# car_onboard.net
KiCad netlist of a schematic drawn in EAGLE
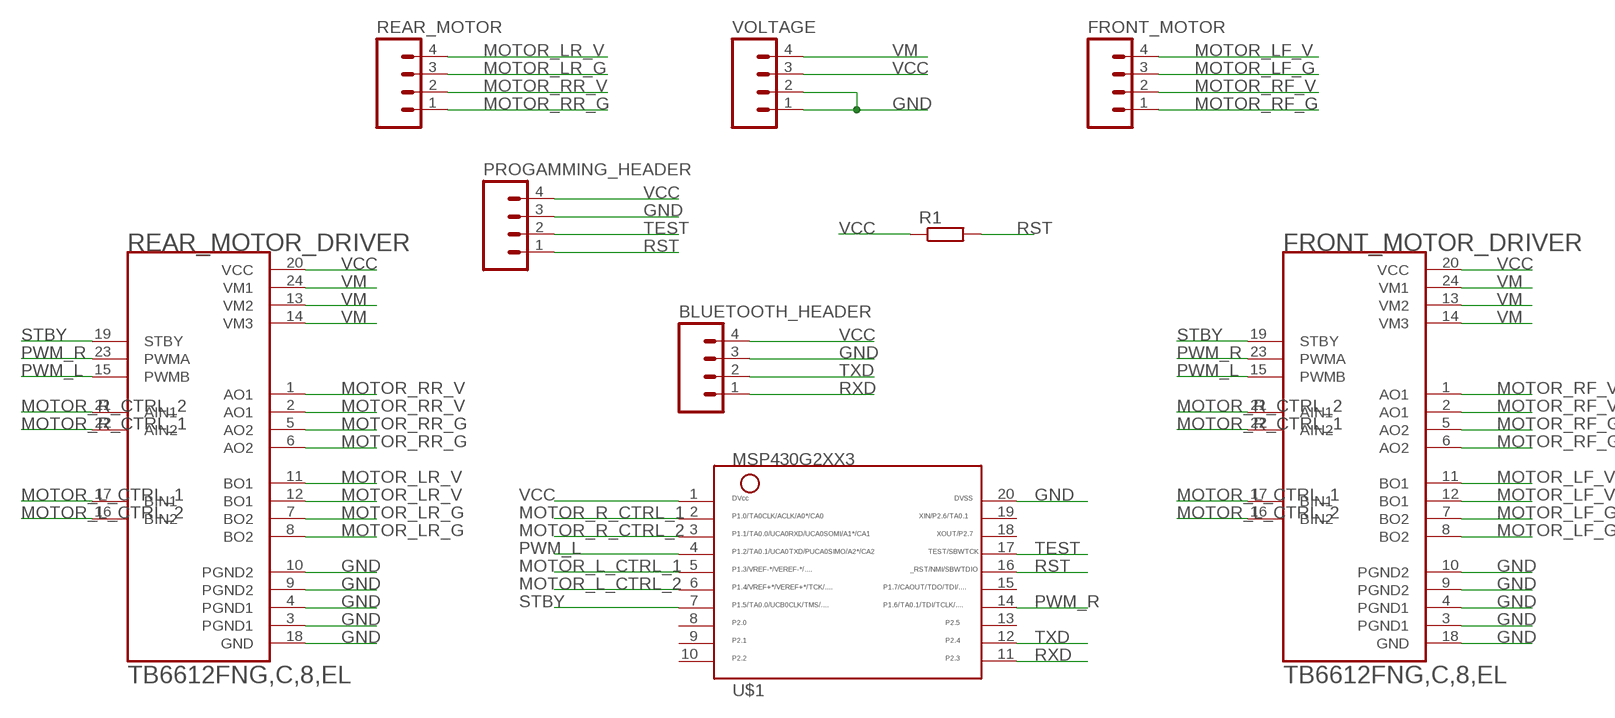
[diagram p0: schematic, sheet 1]

(export (version "E")
  (design (tool "Eeschema 10.0.6"))
  (components
    (comp (ref "BLUETOOTH_HEADER")
      (value "HEADER_1X04LOCK")
      (footprint "eagle-import:1X04_LOCK")
      (libsource (lib "eagle-import") (part "HEADER_1X04LOCK"))
    )
    (comp (ref "FRONT_MOTOR")
      (value "HEADER_1X04LOCK")
      (footprint "eagle-import:1X04_LOCK")
      (libsource (lib "eagle-import") (part "HEADER_1X04LOCK"))
    )
    (comp (ref "FRONT_MOTOR_DRIVER")
      (value "TB6612FNG,C,8,EL")
      (footprint "eagle-import:SOP65P760X160-24N")
      (fields (field (name "MF") "Toshiba"))
      (libsource (lib "eagle-import") (part "TB6612FNG,C,8,EL"))
    )
    (comp (ref "PROGAMMING_HEADER")
      (value "HEADER_1X04LOCK")
      (footprint "eagle-import:1X04_LOCK")
      (libsource (lib "eagle-import") (part "HEADER_1X04LOCK"))
    )
    (comp (ref "R1")
      (value "R-EU_R1206")
      (footprint "eagle-import:R1206")
      (libsource (lib "eagle-import") (part "R-EU_R1206"))
    )
    (comp (ref "REAR_MOTOR")
      (value "HEADER_1X04LOCK")
      (footprint "eagle-import:1X04_LOCK")
      (libsource (lib "eagle-import") (part "HEADER_1X04LOCK"))
    )
    (comp (ref "REAR_MOTOR_DRIVER")
      (value "TB6612FNG,C,8,EL")
      (footprint "eagle-import:SOP65P760X160-24N")
      (fields (field (name "MF") "Toshiba"))
      (libsource (lib "eagle-import") (part "TB6612FNG,C,8,EL"))
    )
    (comp (ref "U$1")
      (value "MSP430G2XX3TSSOP")
      (footprint "eagle-import:PW20")
      (libsource (lib "eagle-import") (part "MSP430G2XX3TSSOP"))
    )
    (comp (ref "VOLTAGE")
      (value "HEADER_1X04LOCK")
      (footprint "eagle-import:1X04_LOCK")
      (libsource (lib "eagle-import") (part "HEADER_1X04LOCK"))
    )
  )
  (nets
    (net (code "1") (name "/GND") (class "Default")
      (node (ref "BLUETOOTH_HEADER") (pin "3") (pinfunction "3_3") (pintype "passive"))
      (node (ref "FRONT_MOTOR_DRIVER") (pin "10") (pinfunction "PGND2_10") (pintype "passive"))
      (node (ref "FRONT_MOTOR_DRIVER") (pin "18") (pinfunction "GND_18") (pintype "passive"))
      (node (ref "FRONT_MOTOR_DRIVER") (pin "3") (pinfunction "PGND1_3") (pintype "passive"))
      (node (ref "FRONT_MOTOR_DRIVER") (pin "4") (pinfunction "PGND1_4") (pintype "passive"))
      (node (ref "FRONT_MOTOR_DRIVER") (pin "9") (pinfunction "PGND2_9") (pintype "passive"))
      (node (ref "PROGAMMING_HEADER") (pin "3") (pinfunction "3_3") (pintype "passive"))
      (node (ref "REAR_MOTOR_DRIVER") (pin "10") (pinfunction "PGND2_10") (pintype "passive"))
      (node (ref "REAR_MOTOR_DRIVER") (pin "18") (pinfunction "GND_18") (pintype "passive"))
      (node (ref "REAR_MOTOR_DRIVER") (pin "3") (pinfunction "PGND1_3") (pintype "passive"))
      (node (ref "REAR_MOTOR_DRIVER") (pin "4") (pinfunction "PGND1_4") (pintype "passive"))
      (node (ref "REAR_MOTOR_DRIVER") (pin "9") (pinfunction "PGND2_9") (pintype "passive"))
      (node (ref "U$1") (pin "20") (pinfunction "20_20") (pintype "bidirectional"))
      (node (ref "VOLTAGE") (pin "1") (pinfunction "1_1") (pintype "passive"))
      (node (ref "VOLTAGE") (pin "2") (pinfunction "2_2") (pintype "passive"))
    )
    (net (code "2") (name "/MOTOR_LF_G") (class "Default")
      (node (ref "FRONT_MOTOR") (pin "3") (pinfunction "3_3") (pintype "passive"))
      (node (ref "FRONT_MOTOR_DRIVER") (pin "7") (pinfunction "BO2_7") (pintype "output"))
      (node (ref "FRONT_MOTOR_DRIVER") (pin "8") (pinfunction "BO2_8") (pintype "output"))
    )
    (net (code "3") (name "/MOTOR_LF_V") (class "Default")
      (node (ref "FRONT_MOTOR") (pin "4") (pinfunction "4_4") (pintype "passive"))
      (node (ref "FRONT_MOTOR_DRIVER") (pin "11") (pinfunction "BO1_11") (pintype "output"))
      (node (ref "FRONT_MOTOR_DRIVER") (pin "12") (pinfunction "BO1_12") (pintype "output"))
    )
    (net (code "4") (name "/MOTOR_LR_G") (class "Default")
      (node (ref "REAR_MOTOR") (pin "3") (pinfunction "3_3") (pintype "passive"))
      (node (ref "REAR_MOTOR_DRIVER") (pin "7") (pinfunction "BO2_7") (pintype "output"))
      (node (ref "REAR_MOTOR_DRIVER") (pin "8") (pinfunction "BO2_8") (pintype "output"))
    )
    (net (code "5") (name "/MOTOR_LR_V") (class "Default")
      (node (ref "REAR_MOTOR") (pin "4") (pinfunction "4_4") (pintype "passive"))
      (node (ref "REAR_MOTOR_DRIVER") (pin "11") (pinfunction "BO1_11") (pintype "output"))
      (node (ref "REAR_MOTOR_DRIVER") (pin "12") (pinfunction "BO1_12") (pintype "output"))
    )
    (net (code "6") (name "/MOTOR_L_CTRL_1") (class "Default")
      (node (ref "FRONT_MOTOR_DRIVER") (pin "17") (pinfunction "BIN1_17") (pintype "input"))
      (node (ref "REAR_MOTOR_DRIVER") (pin "17") (pinfunction "BIN1_17") (pintype "input"))
      (node (ref "U$1") (pin "5") (pinfunction "5_5") (pintype "bidirectional"))
    )
    (net (code "7") (name "/MOTOR_L_CTRL_2") (class "Default")
      (node (ref "FRONT_MOTOR_DRIVER") (pin "16") (pinfunction "BIN2_16") (pintype "input"))
      (node (ref "REAR_MOTOR_DRIVER") (pin "16") (pinfunction "BIN2_16") (pintype "input"))
      (node (ref "U$1") (pin "6") (pinfunction "6_6") (pintype "bidirectional"))
    )
    (net (code "8") (name "/MOTOR_RF_G") (class "Default")
      (node (ref "FRONT_MOTOR") (pin "1") (pinfunction "1_1") (pintype "passive"))
      (node (ref "FRONT_MOTOR_DRIVER") (pin "5") (pinfunction "AO2_5") (pintype "output"))
      (node (ref "FRONT_MOTOR_DRIVER") (pin "6") (pinfunction "AO2_6") (pintype "output"))
    )
    (net (code "9") (name "/MOTOR_RF_V") (class "Default")
      (node (ref "FRONT_MOTOR") (pin "2") (pinfunction "2_2") (pintype "passive"))
      (node (ref "FRONT_MOTOR_DRIVER") (pin "1") (pinfunction "AO1_1") (pintype "output"))
      (node (ref "FRONT_MOTOR_DRIVER") (pin "2") (pinfunction "AO1_2") (pintype "output"))
    )
    (net (code "10") (name "/MOTOR_RR_G") (class "Default")
      (node (ref "REAR_MOTOR") (pin "1") (pinfunction "1_1") (pintype "passive"))
      (node (ref "REAR_MOTOR_DRIVER") (pin "5") (pinfunction "AO2_5") (pintype "output"))
      (node (ref "REAR_MOTOR_DRIVER") (pin "6") (pinfunction "AO2_6") (pintype "output"))
    )
    (net (code "11") (name "/MOTOR_RR_V") (class "Default")
      (node (ref "REAR_MOTOR") (pin "2") (pinfunction "2_2") (pintype "passive"))
      (node (ref "REAR_MOTOR_DRIVER") (pin "1") (pinfunction "AO1_1") (pintype "output"))
      (node (ref "REAR_MOTOR_DRIVER") (pin "2") (pinfunction "AO1_2") (pintype "output"))
    )
    (net (code "12") (name "/MOTOR_R_CTRL_1") (class "Default")
      (node (ref "FRONT_MOTOR_DRIVER") (pin "22") (pinfunction "AIN2_22") (pintype "input"))
      (node (ref "REAR_MOTOR_DRIVER") (pin "22") (pinfunction "AIN2_22") (pintype "input"))
      (node (ref "U$1") (pin "2") (pinfunction "2_2") (pintype "bidirectional"))
    )
    (net (code "13") (name "/MOTOR_R_CTRL_2") (class "Default")
      (node (ref "FRONT_MOTOR_DRIVER") (pin "21") (pinfunction "AIN1_21") (pintype "input"))
      (node (ref "REAR_MOTOR_DRIVER") (pin "21") (pinfunction "AIN1_21") (pintype "input"))
      (node (ref "U$1") (pin "3") (pinfunction "3_3") (pintype "bidirectional"))
    )
    (net (code "14") (name "/PWM_L") (class "Default")
      (node (ref "FRONT_MOTOR_DRIVER") (pin "15") (pinfunction "PWMB_15") (pintype "input"))
      (node (ref "REAR_MOTOR_DRIVER") (pin "15") (pinfunction "PWMB_15") (pintype "input"))
      (node (ref "U$1") (pin "4") (pinfunction "4_4") (pintype "bidirectional"))
    )
    (net (code "15") (name "/PWM_R") (class "Default")
      (node (ref "FRONT_MOTOR_DRIVER") (pin "23") (pinfunction "PWMA_23") (pintype "input"))
      (node (ref "REAR_MOTOR_DRIVER") (pin "23") (pinfunction "PWMA_23") (pintype "input"))
      (node (ref "U$1") (pin "14") (pinfunction "14_14") (pintype "bidirectional"))
    )
    (net (code "16") (name "/RST") (class "Default")
      (node (ref "PROGAMMING_HEADER") (pin "1") (pinfunction "1_1") (pintype "passive"))
      (node (ref "R1") (pin "2") (pinfunction "2_2") (pintype "passive"))
      (node (ref "U$1") (pin "16") (pinfunction "16_16") (pintype "bidirectional"))
    )
    (net (code "17") (name "/RXD") (class "Default")
      (node (ref "BLUETOOTH_HEADER") (pin "1") (pinfunction "1_1") (pintype "passive"))
      (node (ref "U$1") (pin "11") (pinfunction "11_11") (pintype "bidirectional"))
    )
    (net (code "18") (name "/STBY") (class "Default")
      (node (ref "FRONT_MOTOR_DRIVER") (pin "19") (pinfunction "STBY_19") (pintype "input"))
      (node (ref "REAR_MOTOR_DRIVER") (pin "19") (pinfunction "STBY_19") (pintype "input"))
      (node (ref "U$1") (pin "7") (pinfunction "7_7") (pintype "bidirectional"))
    )
    (net (code "19") (name "/TEST") (class "Default")
      (node (ref "PROGAMMING_HEADER") (pin "2") (pinfunction "2_2") (pintype "passive"))
      (node (ref "U$1") (pin "17") (pinfunction "17_17") (pintype "bidirectional"))
    )
    (net (code "20") (name "/TXD") (class "Default")
      (node (ref "BLUETOOTH_HEADER") (pin "2") (pinfunction "2_2") (pintype "passive"))
      (node (ref "U$1") (pin "12") (pinfunction "12_12") (pintype "bidirectional"))
    )
    (net (code "21") (name "/VCC") (class "Default")
      (node (ref "BLUETOOTH_HEADER") (pin "4") (pinfunction "4_4") (pintype "passive"))
      (node (ref "FRONT_MOTOR_DRIVER") (pin "20") (pinfunction "VCC_20") (pintype "power_in"))
      (node (ref "PROGAMMING_HEADER") (pin "4") (pinfunction "4_4") (pintype "passive"))
      (node (ref "R1") (pin "1") (pinfunction "1_1") (pintype "passive"))
      (node (ref "REAR_MOTOR_DRIVER") (pin "20") (pinfunction "VCC_20") (pintype "power_in"))
      (node (ref "U$1") (pin "1") (pinfunction "1_1") (pintype "bidirectional"))
      (node (ref "VOLTAGE") (pin "3") (pinfunction "3_3") (pintype "passive"))
    )
    (net (code "22") (name "/VM") (class "Default")
      (node (ref "FRONT_MOTOR_DRIVER") (pin "13") (pinfunction "VM2_13") (pintype "power_in"))
      (node (ref "FRONT_MOTOR_DRIVER") (pin "14") (pinfunction "VM3_14") (pintype "power_in"))
      (node (ref "FRONT_MOTOR_DRIVER") (pin "24") (pinfunction "VM1_24") (pintype "power_in"))
      (node (ref "REAR_MOTOR_DRIVER") (pin "13") (pinfunction "VM2_13") (pintype "power_in"))
      (node (ref "REAR_MOTOR_DRIVER") (pin "14") (pinfunction "VM3_14") (pintype "power_in"))
      (node (ref "REAR_MOTOR_DRIVER") (pin "24") (pinfunction "VM1_24") (pintype "power_in"))
      (node (ref "VOLTAGE") (pin "4") (pinfunction "4_4") (pintype "passive"))
    )
    (net (code "23") (name "unconnected-(U$1-Pad8)") (class "Default")
      (node (ref "U$1") (pin "8") (pinfunction "8_8") (pintype "bidirectional"))
    )
    (net (code "24") (name "unconnected-(U$1-Pad9)") (class "Default")
      (node (ref "U$1") (pin "9") (pinfunction "9_9") (pintype "bidirectional"))
    )
    (net (code "25") (name "unconnected-(U$1-Pad10)") (class "Default")
      (node (ref "U$1") (pin "10") (pinfunction "10_10") (pintype "bidirectional"))
    )
    (net (code "26") (name "unconnected-(U$1-Pad13)") (class "Default")
      (node (ref "U$1") (pin "13") (pinfunction "13_13") (pintype "bidirectional"))
    )
    (net (code "27") (name "unconnected-(U$1-Pad15)") (class "Default")
      (node (ref "U$1") (pin "15") (pinfunction "15_15") (pintype "bidirectional"))
    )
    (net (code "28") (name "unconnected-(U$1-Pad18)") (class "Default")
      (node (ref "U$1") (pin "18") (pinfunction "18_18") (pintype "bidirectional"))
    )
    (net (code "29") (name "unconnected-(U$1-Pad19)") (class "Default")
      (node (ref "U$1") (pin "19") (pinfunction "19_19") (pintype "bidirectional"))
    )
  )
)
